# plp-ctop_2c.net
KiCad netlist of a schematic drawn in Altium Designer
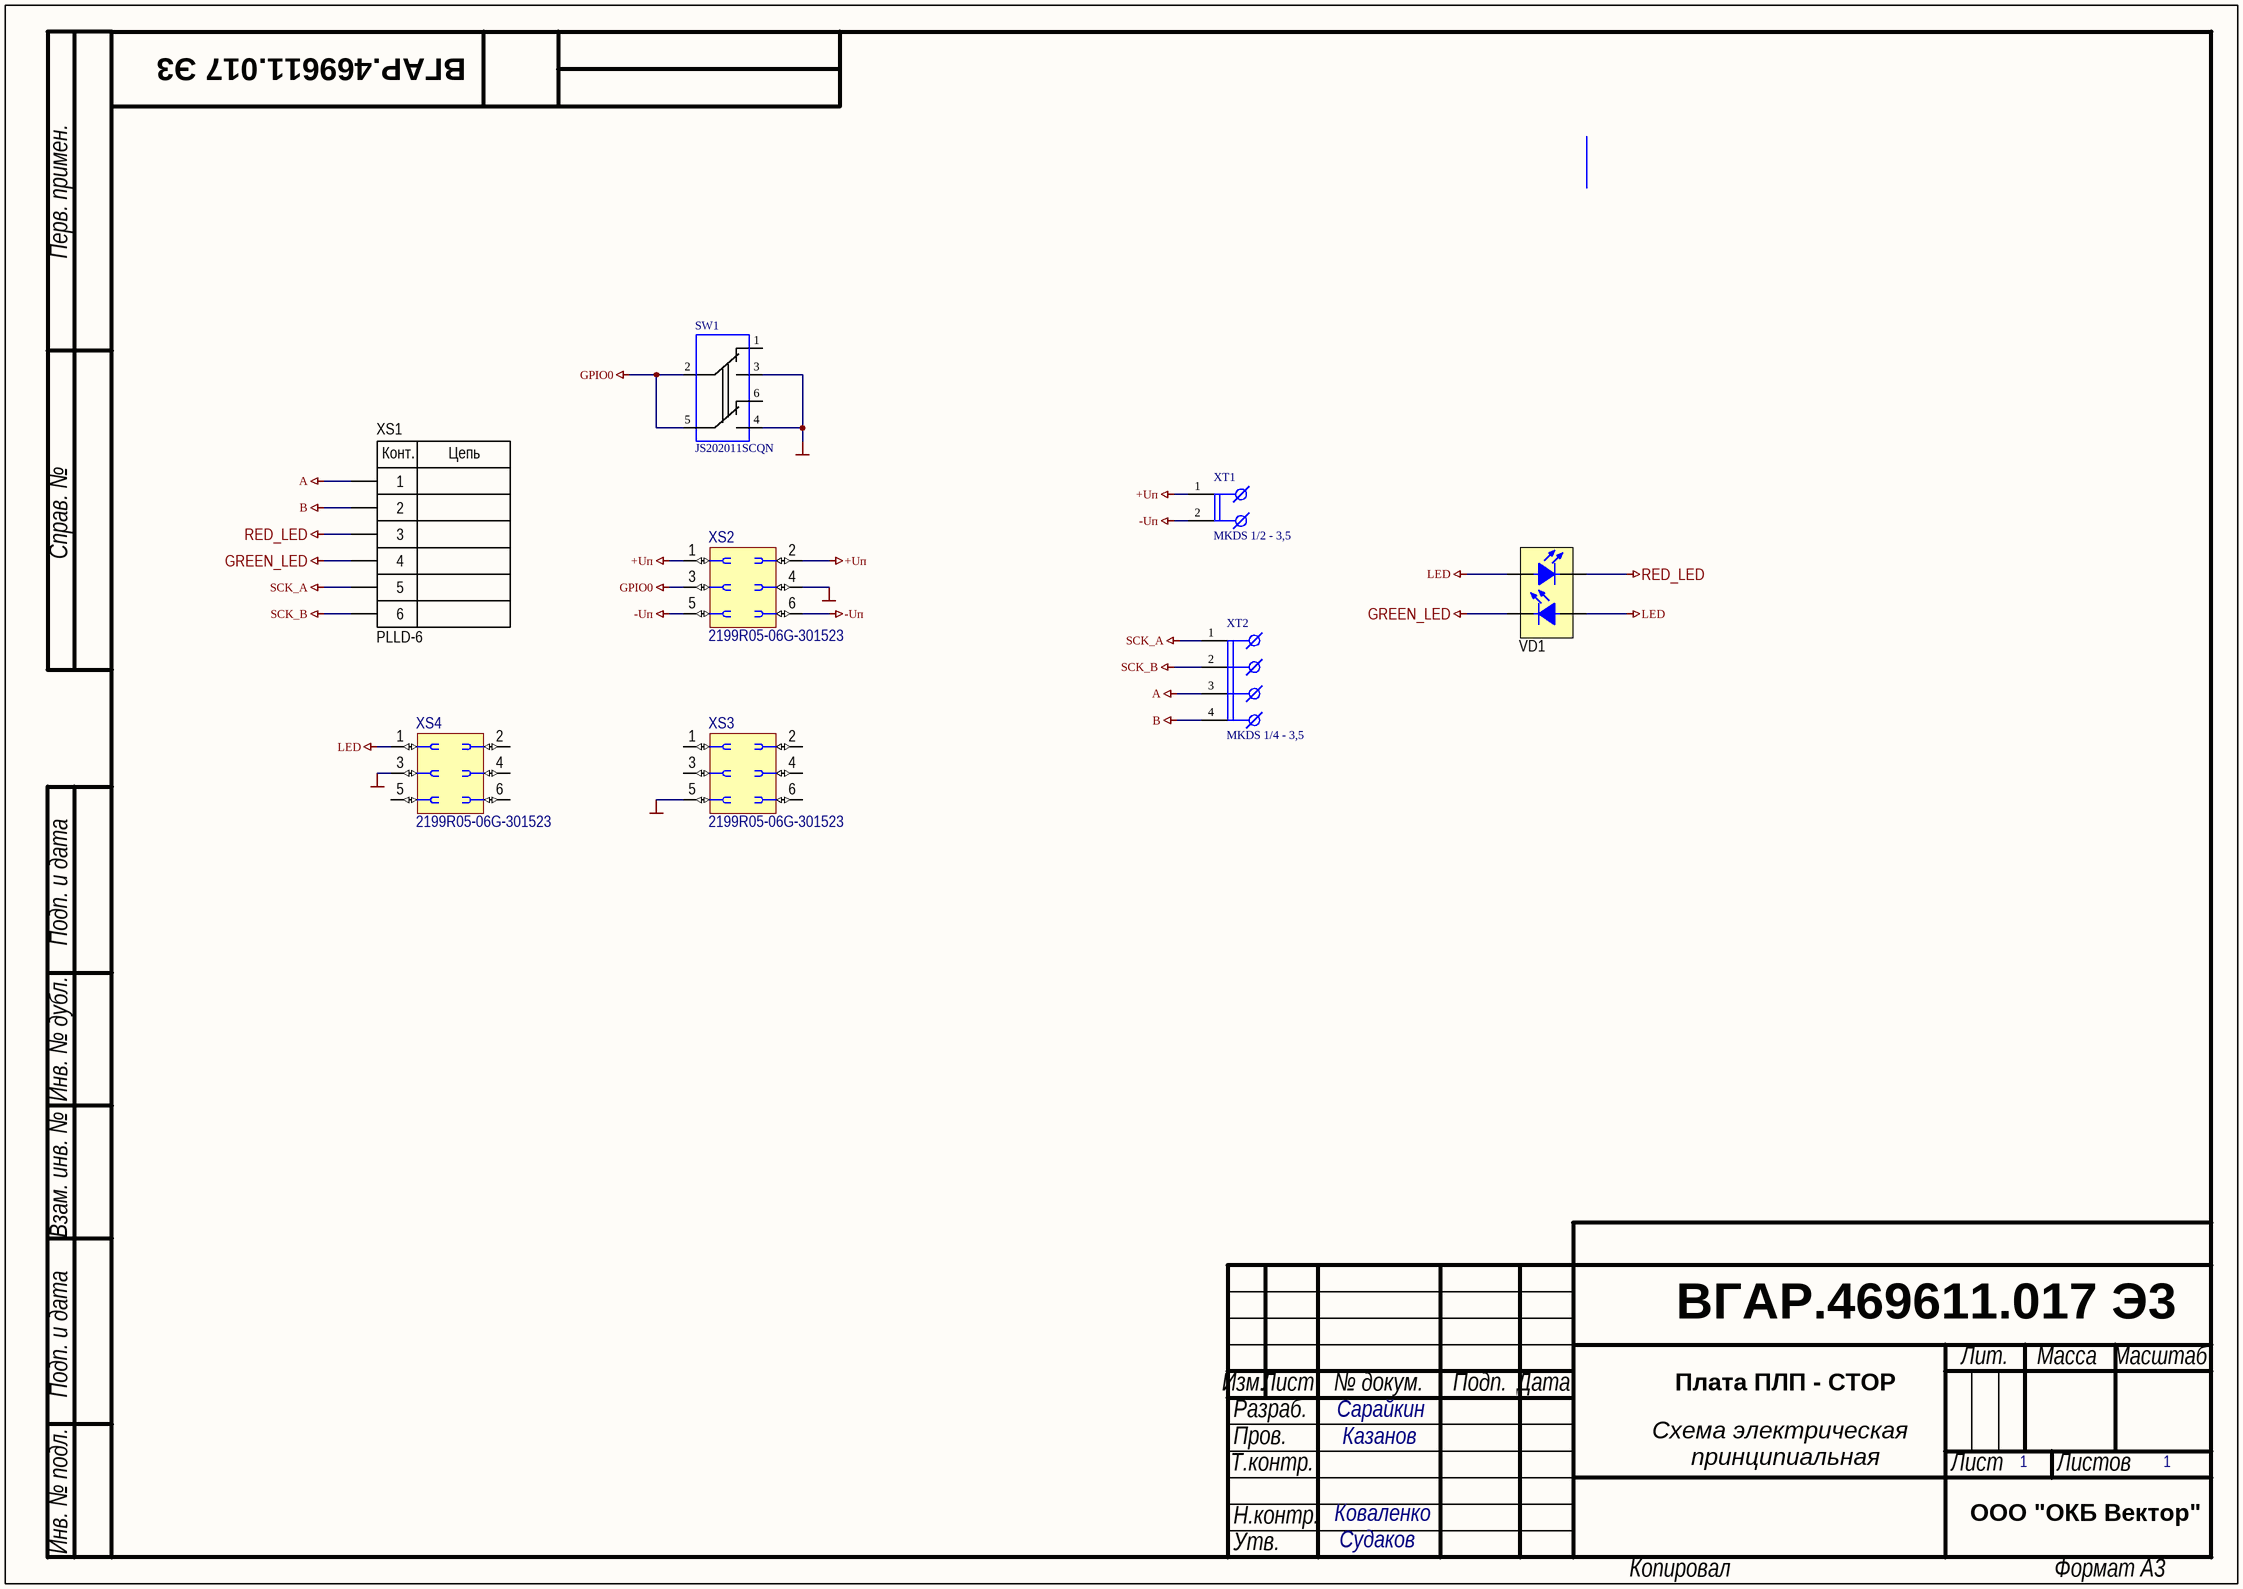
[diagram p0: plp-ctop_2c.SchDoc]

(export (version "E")
  (design (tool "Eeschema 10.0.6"))
  (components
    (comp (ref "SW1")
      (value "JS202011SCQN")
      (footprint "JS202011SCQN")
      (description "Переключатель")
      (fields
        (field (name "MANUFACTURER") "C&K Component")
        (field (name "REPLACEMENTPART1PARTNUMBER") "is-1390")
      )
      (libsource (lib "Switch") (part "JS202011SCQN"))
    )
    (comp (ref "VD1")
      (value "Dual LED")
      (footprint "KAA-3528")
      (description "2-1 RED, 4-3 GREEN")
      (libsource (lib "diode") (part "Dual LED"))
    )
    (comp (ref "XS1")
      (value "PLLD-6")
      (footprint "CON: PLL-6(2x3R1.27female)")
      (description "Step 1.27")
      (libsource (lib "connector") (part "PLLD-6(Female)"))
    )
    (comp (ref "XS2")
      (value "2199R05-06G-301523")
      (footprint "CON: PLL-6(2x3R1.27female)")
      (description "Step 1.27")
      (libsource (lib "connector") (part "2199R05-06G-301523In"))
    )
    (comp (ref "XS3")
      (value "2199R05-06G-301523")
      (footprint "CON: PLL-6(2x3R1.27female)")
      (description "Step 1.27")
      (libsource (lib "connector") (part "2199R05-06G-301523In"))
    )
    (comp (ref "XS4")
      (value "2199R05-06G-301523")
      (footprint "CON: PLL-6(2x3R1.27female)")
      (description "Step 1.27")
      (libsource (lib "connector") (part "2199R05-06G-301523In"))
    )
    (comp (ref "XT1")
      (value "MKDS 1/2 - 3,5")
      (footprint "MKDS 1/2 - 3,5")
      (libsource (lib "Phoenixcontact Terminal Block") (part "MKDS 1/2 - 3,5"))
    )
    (comp (ref "XT2")
      (value "MKDS 1/4 - 3,5")
      (footprint "MKDS 1/4 - 3,5")
      (libsource (lib "Phoenixcontact Terminal Block") (part "MKDS 1/4 - 3,5"))
    )
  )
  (nets
    (net (code "1") (name "+Uп") (class "Default")
      (node (ref "XS2") (pin "1") (pinfunction "1_1") (pintype "bidirectional"))
      (node (ref "XS2") (pin "2") (pinfunction "2_2") (pintype "bidirectional"))
      (node (ref "XT1") (pin "1") (pintype "passive"))
    )
    (net (code "2") (name "-Uп") (class "Default")
      (node (ref "XS2") (pin "5") (pinfunction "5_5") (pintype "bidirectional"))
      (node (ref "XS2") (pin "6") (pinfunction "6_6") (pintype "bidirectional"))
      (node (ref "XT1") (pin "2") (pintype "passive"))
    )
    (net (code "3") (name "A") (class "Default")
      (node (ref "XS1") (pin "1") (pinfunction "1_1") (pintype "passive"))
      (node (ref "XT2") (pin "3") (pintype "passive"))
    )
    (net (code "4") (name "B") (class "Default")
      (node (ref "XS1") (pin "2") (pinfunction "2_2") (pintype "passive"))
      (node (ref "XT2") (pin "4") (pinfunction "4_4") (pintype "passive"))
    )
    (net (code "5") (name "GND") (class "Default")
      (node (ref "SW1") (pin "3") (pinfunction "3_3") (pintype "passive"))
      (node (ref "SW1") (pin "4") (pinfunction "4_4") (pintype "passive"))
      (node (ref "XS2") (pin "4") (pinfunction "4_4") (pintype "bidirectional"))
      (node (ref "XS3") (pin "5") (pinfunction "5_5") (pintype "bidirectional"))
      (node (ref "XS4") (pin "3") (pinfunction "3_3") (pintype "bidirectional"))
    )
    (net (code "6") (name "GPIO0") (class "Default")
      (node (ref "SW1") (pin "2") (pinfunction "2_2") (pintype "passive"))
      (node (ref "SW1") (pin "5") (pinfunction "5_5") (pintype "passive"))
      (node (ref "XS2") (pin "3") (pinfunction "3_3") (pintype "bidirectional"))
    )
    (net (code "7") (name "GREEN_LED") (class "Default")
      (node (ref "VD1") (pin "3") (pinfunction "C_3") (pintype "passive"))
      (node (ref "XS1") (pin "4") (pinfunction "4_4") (pintype "passive"))
    )
    (net (code "8") (name "LED") (class "Default")
      (node (ref "VD1") (pin "2") (pinfunction "A_2") (pintype "passive"))
      (node (ref "VD1") (pin "4") (pinfunction "A_4") (pintype "passive"))
      (node (ref "XS4") (pin "1") (pinfunction "1_1") (pintype "bidirectional"))
    )
    (net (code "9") (name "RED_LED") (class "Default")
      (node (ref "VD1") (pin "1") (pinfunction "C_1") (pintype "passive"))
      (node (ref "XS1") (pin "3") (pinfunction "3_3") (pintype "passive"))
    )
    (net (code "10") (name "SCK_A") (class "Default")
      (node (ref "XS1") (pin "5") (pinfunction "5_5") (pintype "passive"))
      (node (ref "XT2") (pin "1") (pintype "passive"))
    )
    (net (code "11") (name "SCK_B") (class "Default")
      (node (ref "XS1") (pin "6") (pinfunction "6_6") (pintype "passive"))
      (node (ref "XT2") (pin "2") (pintype "passive"))
    )
    (net (code "12") (name "unconnected-(SW1-Pad1)") (class "Default")
      (node (ref "SW1") (pin "1") (pinfunction "1_1") (pintype "passive"))
    )
    (net (code "13") (name "unconnected-(SW1-Pad6)") (class "Default")
      (node (ref "SW1") (pin "6") (pinfunction "6_6") (pintype "passive"))
    )
    (net (code "14") (name "unconnected-(XS3-Pad1)") (class "Default")
      (node (ref "XS3") (pin "1") (pinfunction "1_1") (pintype "bidirectional"))
    )
    (net (code "15") (name "unconnected-(XS3-Pad2)") (class "Default")
      (node (ref "XS3") (pin "2") (pinfunction "2_2") (pintype "bidirectional"))
    )
    (net (code "16") (name "unconnected-(XS3-Pad3)") (class "Default")
      (node (ref "XS3") (pin "3") (pinfunction "3_3") (pintype "bidirectional"))
    )
    (net (code "17") (name "unconnected-(XS3-Pad4)") (class "Default")
      (node (ref "XS3") (pin "4") (pinfunction "4_4") (pintype "bidirectional"))
    )
    (net (code "18") (name "unconnected-(XS3-Pad6)") (class "Default")
      (node (ref "XS3") (pin "6") (pinfunction "6_6") (pintype "bidirectional"))
    )
    (net (code "19") (name "unconnected-(XS4-Pad2)") (class "Default")
      (node (ref "XS4") (pin "2") (pinfunction "2_2") (pintype "bidirectional"))
    )
    (net (code "20") (name "unconnected-(XS4-Pad4)") (class "Default")
      (node (ref "XS4") (pin "4") (pinfunction "4_4") (pintype "bidirectional"))
    )
    (net (code "21") (name "unconnected-(XS4-Pad5)") (class "Default")
      (node (ref "XS4") (pin "5") (pinfunction "5_5") (pintype "bidirectional"))
    )
    (net (code "22") (name "unconnected-(XS4-Pad6)") (class "Default")
      (node (ref "XS4") (pin "6") (pinfunction "6_6") (pintype "bidirectional"))
    )
  )
)
